# active-multiples.net
KiCad netlist of a schematic drawn in EAGLE
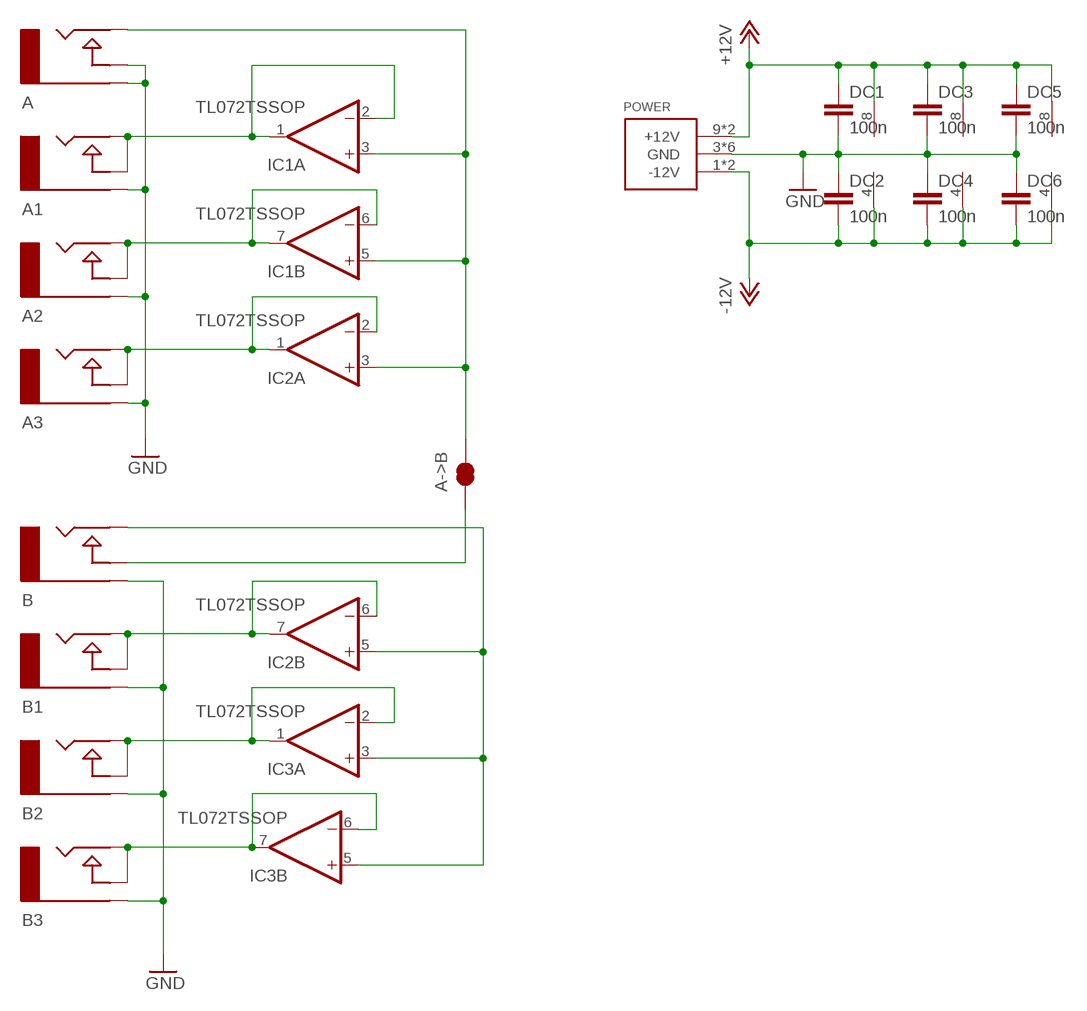
[diagram p0: schematic, sheet 1]

(export (version "E")
  (design (tool "Eeschema 10.0.6"))
  (components
    (comp (ref "A")
      (value "AUDIO-JACKINLINE")
      (footprint "eagle-import:ERTHENVAR-JACK-INLINE")
      (libsource (lib "eagle-import") (part "AUDIO-JACKINLINE"))
    )
    (comp (ref "A->B")
      (value "JUMPER-PAD-2-NC_BY_TRACENO_SILK")
      (footprint "eagle-import:PAD-JUMPER-2-NC_BY_TRACE_NO_SILK")
      (libsource (lib "eagle-import") (part "JUMPER-PAD-2-NC_BY_TRACENO_SILK"))
    )
    (comp (ref "A1")
      (value "AUDIO-JACKINLINE")
      (footprint "eagle-import:ERTHENVAR-JACK-INLINE")
      (libsource (lib "eagle-import") (part "AUDIO-JACKINLINE"))
    )
    (comp (ref "A2")
      (value "AUDIO-JACKINLINE")
      (footprint "eagle-import:ERTHENVAR-JACK-INLINE")
      (libsource (lib "eagle-import") (part "AUDIO-JACKINLINE"))
    )
    (comp (ref "A3")
      (value "AUDIO-JACKINLINE")
      (footprint "eagle-import:ERTHENVAR-JACK-INLINE")
      (libsource (lib "eagle-import") (part "AUDIO-JACKINLINE"))
    )
    (comp (ref "B")
      (value "AUDIO-JACKINLINE")
      (footprint "eagle-import:ERTHENVAR-JACK-INLINE")
      (libsource (lib "eagle-import") (part "AUDIO-JACKINLINE"))
    )
    (comp (ref "B1")
      (value "AUDIO-JACKINLINE")
      (footprint "eagle-import:ERTHENVAR-JACK-INLINE")
      (libsource (lib "eagle-import") (part "AUDIO-JACKINLINE"))
    )
    (comp (ref "B2")
      (value "AUDIO-JACKINLINE")
      (footprint "eagle-import:ERTHENVAR-JACK-INLINE")
      (libsource (lib "eagle-import") (part "AUDIO-JACKINLINE"))
    )
    (comp (ref "B3")
      (value "AUDIO-JACKINLINE")
      (footprint "eagle-import:ERTHENVAR-JACK-INLINE")
      (libsource (lib "eagle-import") (part "AUDIO-JACKINLINE"))
    )
    (comp (ref "DC1")
      (value "100n")
      (footprint "eagle-import:0603-CAP")
      (libsource (lib "eagle-import") (part "CAP0603-CAP"))
    )
    (comp (ref "DC2")
      (value "100n")
      (footprint "eagle-import:0603-CAP")
      (libsource (lib "eagle-import") (part "CAP0603-CAP"))
    )
    (comp (ref "DC3")
      (value "100n")
      (footprint "eagle-import:0603-CAP")
      (libsource (lib "eagle-import") (part "CAP0603-CAP"))
    )
    (comp (ref "DC4")
      (value "100n")
      (footprint "eagle-import:0603-CAP")
      (libsource (lib "eagle-import") (part "CAP0603-CAP"))
    )
    (comp (ref "DC5")
      (value "100n")
      (footprint "eagle-import:0603-CAP")
      (libsource (lib "eagle-import") (part "CAP0603-CAP"))
    )
    (comp (ref "DC6")
      (value "100n")
      (footprint "eagle-import:0603-CAP")
      (libsource (lib "eagle-import") (part "CAP0603-CAP"))
    )
    (comp (ref "IC1")
      (value "TL072TSSOP")
      (footprint "eagle-import:TSSOP8")
      (libsource (lib "eagle-import") (part "TL072TSSOP"))
    )
    (comp (ref "IC2")
      (value "TL072TSSOP")
      (footprint "eagle-import:TSSOP8")
      (libsource (lib "eagle-import") (part "TL072TSSOP"))
    )
    (comp (ref "IC3")
      (value "TL072TSSOP")
      (footprint "eagle-import:TSSOP8")
      (libsource (lib "eagle-import") (part "TL072TSSOP"))
    )
    (comp (ref "POWER")
      (value "POWER_SIMPLE10")
      (footprint "eagle-import:POWER_10")
      (libsource (lib "eagle-import") (part "POWER_SIMPLE10"))
    )
  )
  (nets
    (net (code "1") (name "+12V") (class "Default")
      (node (ref "DC1") (pin "1") (pinfunction "1_1") (pintype "passive"))
      (node (ref "DC3") (pin "1") (pinfunction "1_1") (pintype "passive"))
      (node (ref "DC5") (pin "1") (pinfunction "1_1") (pintype "passive"))
      (node (ref "IC1") (pin "8") (pinfunction "V+_8") (pintype "power_in"))
      (node (ref "IC2") (pin "8") (pinfunction "V+_8") (pintype "power_in"))
      (node (ref "IC3") (pin "8") (pinfunction "V+_8") (pintype "power_in"))
      (node (ref "POWER") (pin "10") (pinfunction "+12V_10") (pintype "bidirectional"))
      (node (ref "POWER") (pin "9") (pinfunction "+12V_9") (pintype "bidirectional"))
    )
    (net (code "2") (name "-12V") (class "Default")
      (node (ref "DC2") (pin "2") (pinfunction "2_2") (pintype "passive"))
      (node (ref "DC4") (pin "2") (pinfunction "2_2") (pintype "passive"))
      (node (ref "DC6") (pin "2") (pinfunction "2_2") (pintype "passive"))
      (node (ref "IC1") (pin "4") (pinfunction "V-_4") (pintype "power_in"))
      (node (ref "IC2") (pin "4") (pinfunction "V-_4") (pintype "power_in"))
      (node (ref "IC3") (pin "4") (pinfunction "V-_4") (pintype "power_in"))
      (node (ref "POWER") (pin "1") (pinfunction "-12V_1") (pintype "bidirectional"))
      (node (ref "POWER") (pin "2") (pinfunction "-12V_2") (pintype "bidirectional"))
    )
    (net (code "3") (name "GND") (class "Default")
      (node (ref "A") (pin "G") (pinfunction "RING_G") (pintype "bidirectional"))
      (node (ref "A") (pin "N") (pinfunction "NORM_N") (pintype "bidirectional"))
      (node (ref "A1") (pin "G") (pinfunction "RING_G") (pintype "bidirectional"))
      (node (ref "A2") (pin "G") (pinfunction "RING_G") (pintype "bidirectional"))
      (node (ref "A3") (pin "G") (pinfunction "RING_G") (pintype "bidirectional"))
      (node (ref "B") (pin "G") (pinfunction "RING_G") (pintype "bidirectional"))
      (node (ref "B1") (pin "G") (pinfunction "RING_G") (pintype "bidirectional"))
      (node (ref "B2") (pin "G") (pinfunction "RING_G") (pintype "bidirectional"))
      (node (ref "B3") (pin "G") (pinfunction "RING_G") (pintype "bidirectional"))
      (node (ref "DC1") (pin "2") (pinfunction "2_2") (pintype "passive"))
      (node (ref "DC2") (pin "1") (pinfunction "1_1") (pintype "passive"))
      (node (ref "DC3") (pin "2") (pinfunction "2_2") (pintype "passive"))
      (node (ref "DC4") (pin "1") (pinfunction "1_1") (pintype "passive"))
      (node (ref "DC5") (pin "2") (pinfunction "2_2") (pintype "passive"))
      (node (ref "DC6") (pin "1") (pinfunction "1_1") (pintype "passive"))
      (node (ref "POWER") (pin "3") (pinfunction "GND_3") (pintype "bidirectional"))
      (node (ref "POWER") (pin "4") (pinfunction "GND_4") (pintype "bidirectional"))
      (node (ref "POWER") (pin "5") (pinfunction "GND_5") (pintype "bidirectional"))
      (node (ref "POWER") (pin "6") (pinfunction "GND_6") (pintype "bidirectional"))
      (node (ref "POWER") (pin "7") (pinfunction "GND_7") (pintype "bidirectional"))
      (node (ref "POWER") (pin "8") (pinfunction "GND_8") (pintype "bidirectional"))
    )
    (net (code "4") (name "Net-(A-TIP)") (class "Default")
      (node (ref "A") (pin "T") (pinfunction "TIP_T") (pintype "bidirectional"))
      (node (ref "A->B") (pin "2") (pinfunction "2_2") (pintype "passive"))
      (node (ref "IC1") (pin "3") (pinfunction "+IN_3") (pintype "input"))
      (node (ref "IC1") (pin "5") (pinfunction "+IN_5") (pintype "input"))
      (node (ref "IC2") (pin "3") (pinfunction "+IN_3") (pintype "input"))
    )
    (net (code "5") (name "Net-(A1-NORM)") (class "Default")
      (node (ref "A1") (pin "N") (pinfunction "NORM_N") (pintype "bidirectional"))
      (node (ref "A1") (pin "T") (pinfunction "TIP_T") (pintype "bidirectional"))
      (node (ref "IC1") (pin "1") (pinfunction "OUT_1") (pintype "output"))
      (node (ref "IC1") (pin "2") (pinfunction "-IN_2") (pintype "input"))
    )
    (net (code "6") (name "Net-(A2-NORM)") (class "Default")
      (node (ref "A2") (pin "N") (pinfunction "NORM_N") (pintype "bidirectional"))
      (node (ref "A2") (pin "T") (pinfunction "TIP_T") (pintype "bidirectional"))
      (node (ref "IC1") (pin "6") (pinfunction "-IN_6") (pintype "input"))
      (node (ref "IC1") (pin "7") (pinfunction "OUT_7") (pintype "output"))
    )
    (net (code "7") (name "Net-(A3-NORM)") (class "Default")
      (node (ref "A3") (pin "N") (pinfunction "NORM_N") (pintype "bidirectional"))
      (node (ref "A3") (pin "T") (pinfunction "TIP_T") (pintype "bidirectional"))
      (node (ref "IC2") (pin "1") (pinfunction "OUT_1") (pintype "output"))
      (node (ref "IC2") (pin "2") (pinfunction "-IN_2") (pintype "input"))
    )
    (net (code "8") (name "Net-(B-NORM)") (class "Default")
      (node (ref "A->B") (pin "1") (pinfunction "1_1") (pintype "passive"))
      (node (ref "B") (pin "N") (pinfunction "NORM_N") (pintype "bidirectional"))
    )
    (net (code "9") (name "Net-(B-TIP)") (class "Default")
      (node (ref "B") (pin "T") (pinfunction "TIP_T") (pintype "bidirectional"))
      (node (ref "IC2") (pin "5") (pinfunction "+IN_5") (pintype "input"))
      (node (ref "IC3") (pin "3") (pinfunction "+IN_3") (pintype "input"))
      (node (ref "IC3") (pin "5") (pinfunction "+IN_5") (pintype "input"))
    )
    (net (code "10") (name "Net-(B1-NORM)") (class "Default")
      (node (ref "B1") (pin "N") (pinfunction "NORM_N") (pintype "bidirectional"))
      (node (ref "B1") (pin "T") (pinfunction "TIP_T") (pintype "bidirectional"))
      (node (ref "IC2") (pin "6") (pinfunction "-IN_6") (pintype "input"))
      (node (ref "IC2") (pin "7") (pinfunction "OUT_7") (pintype "output"))
    )
    (net (code "11") (name "Net-(B2-NORM)") (class "Default")
      (node (ref "B2") (pin "N") (pinfunction "NORM_N") (pintype "bidirectional"))
      (node (ref "B2") (pin "T") (pinfunction "TIP_T") (pintype "bidirectional"))
      (node (ref "IC3") (pin "1") (pinfunction "OUT_1") (pintype "output"))
      (node (ref "IC3") (pin "2") (pinfunction "-IN_2") (pintype "input"))
    )
    (net (code "12") (name "Net-(B3-NORM)") (class "Default")
      (node (ref "B3") (pin "N") (pinfunction "NORM_N") (pintype "bidirectional"))
      (node (ref "B3") (pin "T") (pinfunction "TIP_T") (pintype "bidirectional"))
      (node (ref "IC3") (pin "6") (pinfunction "-IN_6") (pintype "input"))
      (node (ref "IC3") (pin "7") (pinfunction "OUT_7") (pintype "output"))
    )
  )
)
